# Sheet4550_2.net
KiCad netlist of a schematic drawn in Altium Designer
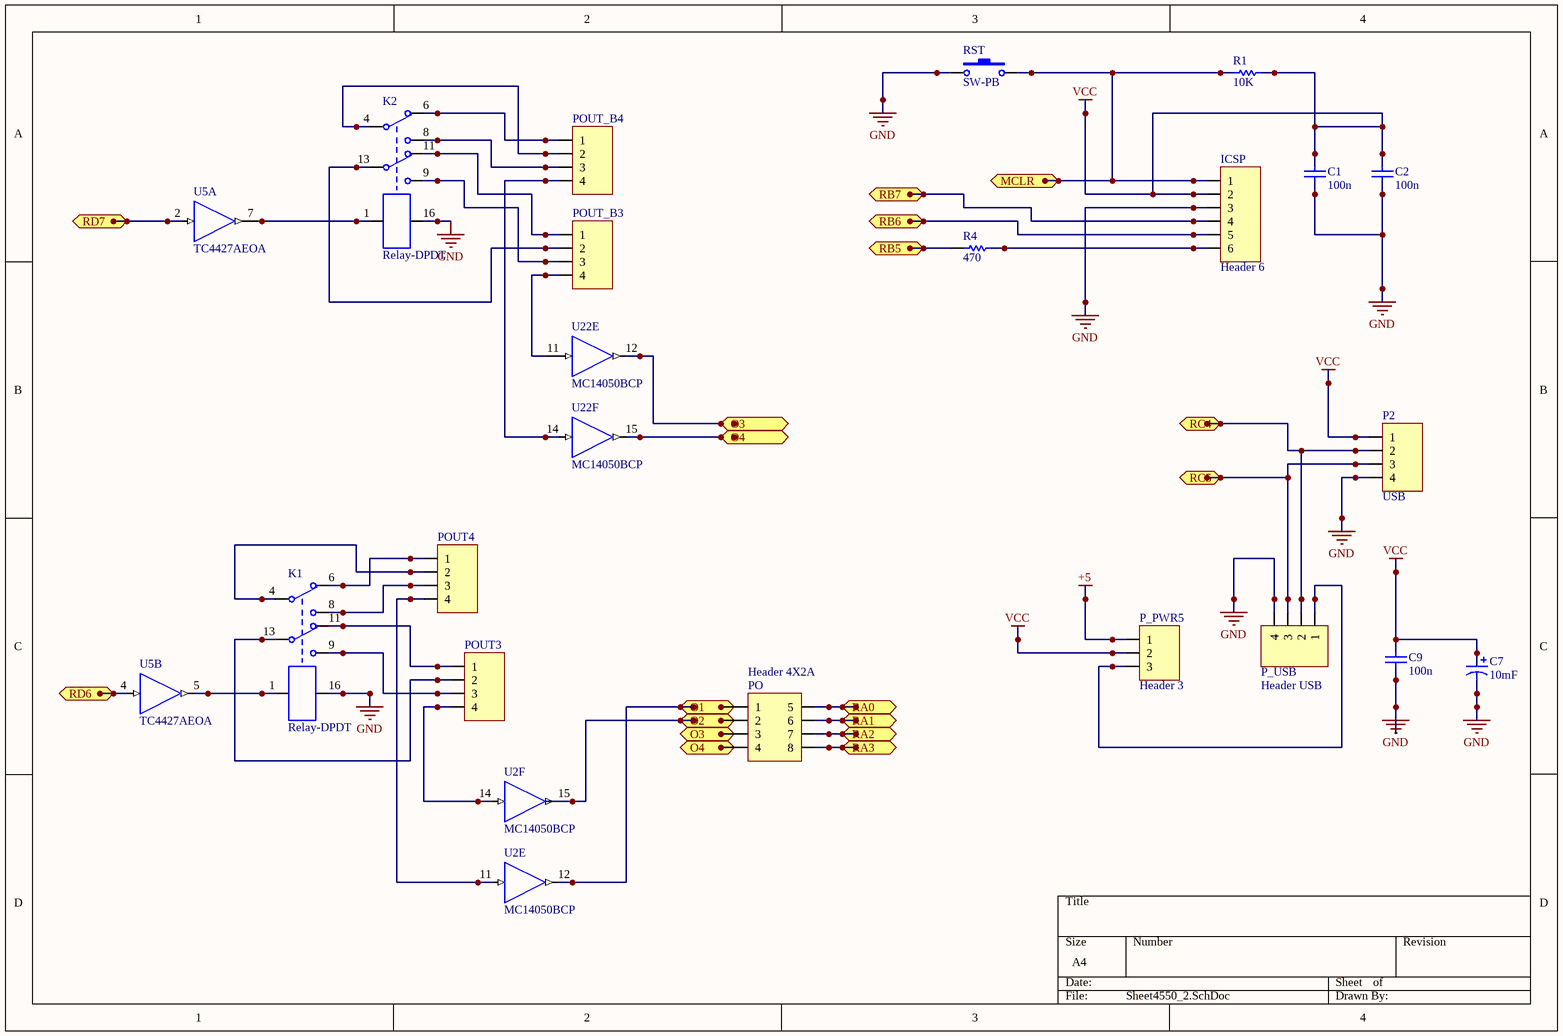
[diagram p0: Sheet4550_2.SchDoc]

(export (version "E")
  (design (tool "Eeschema 10.0.6"))
  (components
    (comp (ref "C1")
      (value "100n")
      (footprint "CAPC2012L")
      (description "Capacitor (Semiconductor SIM Model)")
      (fields (field (name "PUBLISHER") "Altium Limited"))
      (libsource (lib "Miscellaneous Devices") (part "Cap Semi"))
    )
    (comp (ref "C2")
      (value "100n")
      (footprint "CAPC2012L")
      (description "Capacitor (Semiconductor SIM Model)")
      (fields (field (name "PUBLISHER") "Altium Limited"))
      (libsource (lib "Miscellaneous Devices") (part "Cap Semi"))
    )
    (comp (ref "C7")
      (value "10mF")
      (footprint "CAPC5764L")
      (description "Polarized Capacitor (Radial)")
      (fields (field (name "PUBLISHER") "Altium Limited"))
      (libsource (lib "Miscellaneous Devices") (part "Cap Pol1"))
    )
    (comp (ref "C9")
      (value "100n")
      (footprint "CAPC2012L")
      (description "Capacitor (Semiconductor SIM Model)")
      (fields (field (name "PUBLISHER") "Altium Limited"))
      (libsource (lib "Miscellaneous Devices") (part "Cap Semi"))
    )
    (comp (ref "ICSP")
      (value "Header 6")
      (footprint "HDR1X6")
      (description "Header, 6-Pin")
      (fields (field (name "PUBLISHER") "Altium Limited"))
      (libsource (lib "Miscellaneous Connectors") (part "Header 6"))
    )
    (comp (ref "K1")
      (value "Relay-DPDT")
      (footprint "DIP-16-KEY")
      (description "Dual-Pole Dual-Throw Relay")
      (fields (field (name "PUBLISHER") "Altium Limited"))
      (libsource (lib "PCB_4550") (part "Relay-DPDT"))
    )
    (comp (ref "K2")
      (value "Relay-DPDT")
      (footprint "DIP-16-KEY")
      (description "Dual-Pole Dual-Throw Relay")
      (fields (field (name "PUBLISHER") "Altium Limited"))
      (libsource (lib "PCB_4550") (part "Relay-DPDT"))
    )
    (comp (ref "P2")
      (value "USB")
      (footprint "HDR1X4")
      (description "Header, 4-Pin")
      (fields (field (name "PUBLISHER") "Altium Limited"))
      (libsource (lib "PCB_4550") (part "Header 4"))
    )
    (comp (ref "PO")
      (value "Header 4X2A")
      (footprint "HDR2X4_CEN")
      (description "Header, 4-Pin, Dual row")
      (fields (field (name "PUBLISHER") "Altium Limited"))
      (libsource (lib "Miscellaneous Connectors") (part "Header 4X2A"))
    )
    (comp (ref "POUT3")
      (value "Big1")
      (footprint "BIG4")
      (description "Header, 4-Pin")
      (fields (field (name "PUBLISHER") "Altium Limited"))
      (libsource (lib "PCB_4550") (part "Header 4"))
    )
    (comp (ref "POUT4")
      (value "Big1")
      (footprint "BIG4")
      (description "Header, 4-Pin")
      (fields (field (name "PUBLISHER") "Altium Limited"))
      (libsource (lib "PCB_4550") (part "Header 4"))
    )
    (comp (ref "POUT_B3")
      (value "Big1")
      (footprint "BIG4")
      (description "Header, 4-Pin")
      (fields (field (name "PUBLISHER") "Altium Limited"))
      (libsource (lib "PCB_4550") (part "Header 4"))
    )
    (comp (ref "POUT_B4")
      (value "Big1")
      (footprint "BIG4")
      (description "Header, 4-Pin")
      (fields (field (name "PUBLISHER") "Altium Limited"))
      (libsource (lib "PCB_4550") (part "Header 4"))
    )
    (comp (ref "P_PWR5")
      (value "Header 3")
      (footprint "HDR1X3")
      (description "Header, 3-Pin")
      (fields (field (name "PUBLISHER") "Altium Limited"))
      (libsource (lib "Miscellaneous Connectors") (part "Header 3"))
    )
    (comp (ref "P_USB")
      (value "Header USB")
      (footprint "USB2.5-2H4D")
      (description "Header, 4-Pin")
      (fields (field (name "PUBLISHER") "Altium Limited"))
      (libsource (lib "PCB_4550") (part "Header_USB"))
    )
    (comp (ref "R1")
      (value "10K")
      (footprint "RESC3216L")
      (description "Semiconductor Resistor")
      (fields (field (name "PUBLISHER") "Altium Limited"))
      (libsource (lib "Miscellaneous Devices") (part "Res Semi"))
    )
    (comp (ref "R4")
      (value "470")
      (footprint "RESC3216L")
      (description "Semiconductor Resistor")
      (fields (field (name "PUBLISHER") "Altium Limited"))
      (libsource (lib "Miscellaneous Devices") (part "Res Semi"))
    )
    (comp (ref "RST")
      (value "SW-PB")
      (footprint "SPST-2")
      (description "Switch")
      (fields (field (name "PUBLISHER") "Altium Limited"))
      (libsource (lib "Miscellaneous Devices") (part "SW-PB"))
    )
    (comp (ref "U2")
      (value "MC14050BCP")
      (footprint "648-08")
      (description "Hex Non-Inverting Buffer")
      (fields (field (name "PUBLISHER") "Altium Limited"))
      (libsource (lib "ON Semi Logic Buffer Line Driver") (part "MC14050BCP"))
    )
    (comp (ref "U5")
      (value "TC4427AEOA")
      (footprint "SOIC-OA8_N")
      (description "1.5A Dual High-Speed Power MOSFET Driver, Non-Inverting, Industrial Temperature")
      (fields (field (name "PUBLISHER") "Altium Limited"))
      (libsource (lib "Microchip Power Mgt MOSFET Driver") (part "TC4427AEOA"))
    )
    (comp (ref "U22")
      (value "MC14050BCP")
      (footprint "648-08")
      (description "Hex Non-Inverting Buffer")
      (fields (field (name "PUBLISHER") "Altium Limited"))
      (libsource (lib "ON Semi Logic Buffer Line Driver") (part "MC14050BCP"))
    )
  )
  (nets
    (net (code "1") (name "+5") (class "Default")
      (node (ref "P_PWR5") (pin "1") (pinfunction "1_1") (pintype "passive"))
    )
    (net (code "2") (name "/MCLR") (class "Default")
      (node (ref "ICSP") (pin "1") (pinfunction "1_1") (pintype "passive"))
      (node (ref "R1") (pin "1") (pinfunction "1_1") (pintype "passive"))
      (node (ref "RST") (pin "2") (pinfunction "2_2") (pintype "passive"))
    )
    (net (code "3") (name "/O1") (class "Default")
      (node (ref "U2") (pin "12") (pinfunction "OUT_12") (pintype "output"))
    )
    (net (code "4") (name "/O2") (class "Default")
      (node (ref "U2") (pin "15") (pinfunction "OUT_15") (pintype "output"))
    )
    (net (code "5") (name "/O3") (class "Default")
      (node (ref "U22") (pin "12") (pinfunction "OUT_12") (pintype "output"))
    )
    (net (code "6") (name "/O4") (class "Default")
      (node (ref "U22") (pin "15") (pinfunction "OUT_15") (pintype "output"))
    )
    (net (code "7") (name "/RA0") (class "Default")
      (node (ref "PO") (pin "5") (pinfunction "5_5") (pintype "passive"))
    )
    (net (code "8") (name "/RA1") (class "Default")
      (node (ref "PO") (pin "6") (pinfunction "6_6") (pintype "passive"))
    )
    (net (code "9") (name "/RA2") (class "Default")
      (node (ref "PO") (pin "7") (pinfunction "7_7") (pintype "passive"))
    )
    (net (code "10") (name "/RA3") (class "Default")
      (node (ref "PO") (pin "8") (pinfunction "8_8") (pintype "passive"))
    )
    (net (code "11") (name "/RB5") (class "Default")
      (node (ref "R4") (pin "1") (pinfunction "1_1") (pintype "passive"))
    )
    (net (code "12") (name "/RB6") (class "Default")
      (node (ref "ICSP") (pin "5") (pinfunction "5_5") (pintype "passive"))
    )
    (net (code "13") (name "/RB7") (class "Default")
      (node (ref "ICSP") (pin "4") (pinfunction "4_4") (pintype "passive"))
    )
    (net (code "14") (name "/RC4") (class "Default")
      (node (ref "P2") (pin "2") (pinfunction "2_2") (pintype "passive"))
      (node (ref "P_USB") (pin "2") (pinfunction "2_2") (pintype "passive"))
    )
    (net (code "15") (name "/RC5") (class "Default")
      (node (ref "P2") (pin "3") (pinfunction "3_3") (pintype "passive"))
      (node (ref "P_USB") (pin "3") (pinfunction "3_3") (pintype "passive"))
    )
    (net (code "16") (name "/RD6") (class "Default")
      (node (ref "U5") (pin "4") (pinfunction "INB_4") (pintype "input"))
    )
    (net (code "17") (name "/RD7") (class "Default")
      (node (ref "U5") (pin "2") (pinfunction "INA_2") (pintype "input"))
    )
    (net (code "18") (name "GND") (class "Default")
      (node (ref "C1") (pin "1") (pinfunction "1_1") (pintype "passive"))
      (node (ref "C2") (pin "1") (pinfunction "1_1") (pintype "passive"))
      (node (ref "C7") (pin "2") (pinfunction "2_2") (pintype "passive"))
      (node (ref "C9") (pin "1") (pinfunction "1_1") (pintype "passive"))
      (node (ref "ICSP") (pin "3") (pinfunction "3_3") (pintype "passive"))
      (node (ref "K1") (pin "16") (pinfunction "16_16") (pintype "passive"))
      (node (ref "K2") (pin "16") (pinfunction "16_16") (pintype "passive"))
      (node (ref "P2") (pin "4") (pinfunction "4_4") (pintype "passive"))
      (node (ref "P_USB") (pin "4") (pinfunction "4_4") (pintype "passive"))
      (node (ref "RST") (pin "1") (pinfunction "1_1") (pintype "passive"))
      (node (ref "U2") (pin "8") (pinfunction "GND_8") (pintype "power_in"))
      (node (ref "U22") (pin "8") (pinfunction "GND_8") (pintype "power_in"))
    )
    (net (code "19") (name "Net-(ICSP-Pad6)") (class "Default")
      (node (ref "ICSP") (pin "6") (pinfunction "6_6") (pintype "passive"))
      (node (ref "R4") (pin "2") (pinfunction "2_2") (pintype "passive"))
    )
    (net (code "20") (name "Net-(K1-Pad4)") (class "Default")
      (node (ref "K1") (pin "4") (pinfunction "4_4") (pintype "passive"))
      (node (ref "POUT4") (pin "2") (pinfunction "2_2") (pintype "passive"))
    )
    (net (code "21") (name "Net-(K1-Pad6)") (class "Default")
      (node (ref "K1") (pin "6") (pinfunction "6_6") (pintype "passive"))
      (node (ref "POUT4") (pin "1") (pinfunction "1_1") (pintype "passive"))
    )
    (net (code "22") (name "Net-(K1-Pad8)") (class "Default")
      (node (ref "K1") (pin "8") (pinfunction "8_8") (pintype "passive"))
      (node (ref "POUT4") (pin "3") (pinfunction "3_3") (pintype "passive"))
    )
    (net (code "23") (name "Net-(K1-Pad9)") (class "Default")
      (node (ref "K1") (pin "9") (pinfunction "9_9") (pintype "passive"))
      (node (ref "POUT3") (pin "3") (pinfunction "3_3") (pintype "passive"))
    )
    (net (code "24") (name "Net-(K1-Pad11)") (class "Default")
      (node (ref "K1") (pin "11") (pinfunction "11_11") (pintype "passive"))
      (node (ref "POUT3") (pin "1") (pinfunction "1_1") (pintype "passive"))
    )
    (net (code "25") (name "Net-(K1-Pad13)") (class "Default")
      (node (ref "K1") (pin "13") (pinfunction "13_13") (pintype "passive"))
      (node (ref "POUT3") (pin "2") (pinfunction "2_2") (pintype "passive"))
    )
    (net (code "26") (name "Net-(K2-Pad4)") (class "Default")
      (node (ref "K2") (pin "4") (pinfunction "4_4") (pintype "passive"))
      (node (ref "POUT_B4") (pin "2") (pinfunction "2_2") (pintype "passive"))
    )
    (net (code "27") (name "Net-(K2-Pad6)") (class "Default")
      (node (ref "K2") (pin "6") (pinfunction "6_6") (pintype "passive"))
      (node (ref "POUT_B4") (pin "1") (pinfunction "1_1") (pintype "passive"))
    )
    (net (code "28") (name "Net-(K2-Pad8)") (class "Default")
      (node (ref "K2") (pin "8") (pinfunction "8_8") (pintype "passive"))
      (node (ref "POUT_B4") (pin "3") (pinfunction "3_3") (pintype "passive"))
    )
    (net (code "29") (name "Net-(K2-Pad9)") (class "Default")
      (node (ref "K2") (pin "9") (pinfunction "9_9") (pintype "passive"))
      (node (ref "POUT_B3") (pin "3") (pinfunction "3_3") (pintype "passive"))
    )
    (net (code "30") (name "Net-(K2-Pad11)") (class "Default")
      (node (ref "K2") (pin "11") (pinfunction "11_11") (pintype "passive"))
      (node (ref "POUT_B3") (pin "1") (pinfunction "1_1") (pintype "passive"))
    )
    (net (code "31") (name "Net-(K2-Pad13)") (class "Default")
      (node (ref "K2") (pin "13") (pinfunction "13_13") (pintype "passive"))
      (node (ref "POUT_B3") (pin "2") (pinfunction "2_2") (pintype "passive"))
    )
    (net (code "32") (name "Net-(P_PWR5-Pad3)") (class "Default")
      (node (ref "P_PWR5") (pin "3") (pinfunction "3_3") (pintype "passive"))
      (node (ref "P_USB") (pin "1") (pinfunction "1_1") (pintype "passive"))
    )
    (net (code "33") (name "Net-(U2E-IN)") (class "Default")
      (node (ref "POUT4") (pin "4") (pinfunction "4_4") (pintype "passive"))
      (node (ref "U2") (pin "11") (pinfunction "IN_11") (pintype "input"))
    )
    (net (code "34") (name "Net-(U2F-IN)") (class "Default")
      (node (ref "POUT3") (pin "4") (pinfunction "4_4") (pintype "passive"))
      (node (ref "U2") (pin "14") (pinfunction "IN_14") (pintype "input"))
    )
    (net (code "35") (name "Net-(U5A-OUTA)") (class "Default")
      (node (ref "K2") (pin "1") (pinfunction "1_1") (pintype "passive"))
      (node (ref "U5") (pin "7") (pinfunction "OUTA_7") (pintype "output"))
    )
    (net (code "36") (name "Net-(U5B-OUTB)") (class "Default")
      (node (ref "K1") (pin "1") (pinfunction "1_1") (pintype "passive"))
      (node (ref "U5") (pin "5") (pinfunction "OUTB_5") (pintype "output"))
    )
    (net (code "37") (name "Net-(U22E-IN)") (class "Default")
      (node (ref "POUT_B3") (pin "4") (pinfunction "4_4") (pintype "passive"))
      (node (ref "U22") (pin "11") (pinfunction "IN_11") (pintype "input"))
    )
    (net (code "38") (name "Net-(U22F-IN)") (class "Default")
      (node (ref "POUT_B4") (pin "4") (pinfunction "4_4") (pintype "passive"))
      (node (ref "U22") (pin "14") (pinfunction "IN_14") (pintype "input"))
    )
    (net (code "39") (name "VCC") (class "Default")
      (node (ref "C1") (pin "2") (pinfunction "2_2") (pintype "passive"))
      (node (ref "C2") (pin "2") (pinfunction "2_2") (pintype "passive"))
      (node (ref "C7") (pin "1") (pinfunction "1_1") (pintype "passive"))
      (node (ref "C9") (pin "2") (pinfunction "2_2") (pintype "passive"))
      (node (ref "ICSP") (pin "2") (pinfunction "2_2") (pintype "passive"))
      (node (ref "P2") (pin "1") (pinfunction "1_1") (pintype "passive"))
      (node (ref "P_PWR5") (pin "2") (pinfunction "2_2") (pintype "passive"))
      (node (ref "R1") (pin "2") (pinfunction "2_2") (pintype "passive"))
    )
    (net (code "40") (name "VDD") (class "Default")
      (node (ref "U2") (pin "1") (pinfunction "VDD_1") (pintype "power_in"))
      (node (ref "U22") (pin "1") (pinfunction "VDD_1") (pintype "power_in"))
    )
    (net (code "41") (name "unconnected-(PO-Pad1)") (class "Default")
      (node (ref "PO") (pin "1") (pinfunction "1_1") (pintype "passive"))
    )
    (net (code "42") (name "unconnected-(PO-Pad2)") (class "Default")
      (node (ref "PO") (pin "2") (pinfunction "2_2") (pintype "passive"))
    )
    (net (code "43") (name "unconnected-(PO-Pad3)") (class "Default")
      (node (ref "PO") (pin "3") (pinfunction "3_3") (pintype "passive"))
    )
    (net (code "44") (name "unconnected-(PO-Pad4)") (class "Default")
      (node (ref "PO") (pin "4") (pinfunction "4_4") (pintype "passive"))
    )
  )
)
